# BW1098OBC_RIGHT_OV9282.net
KiCad netlist of a schematic drawn in Altium Designer
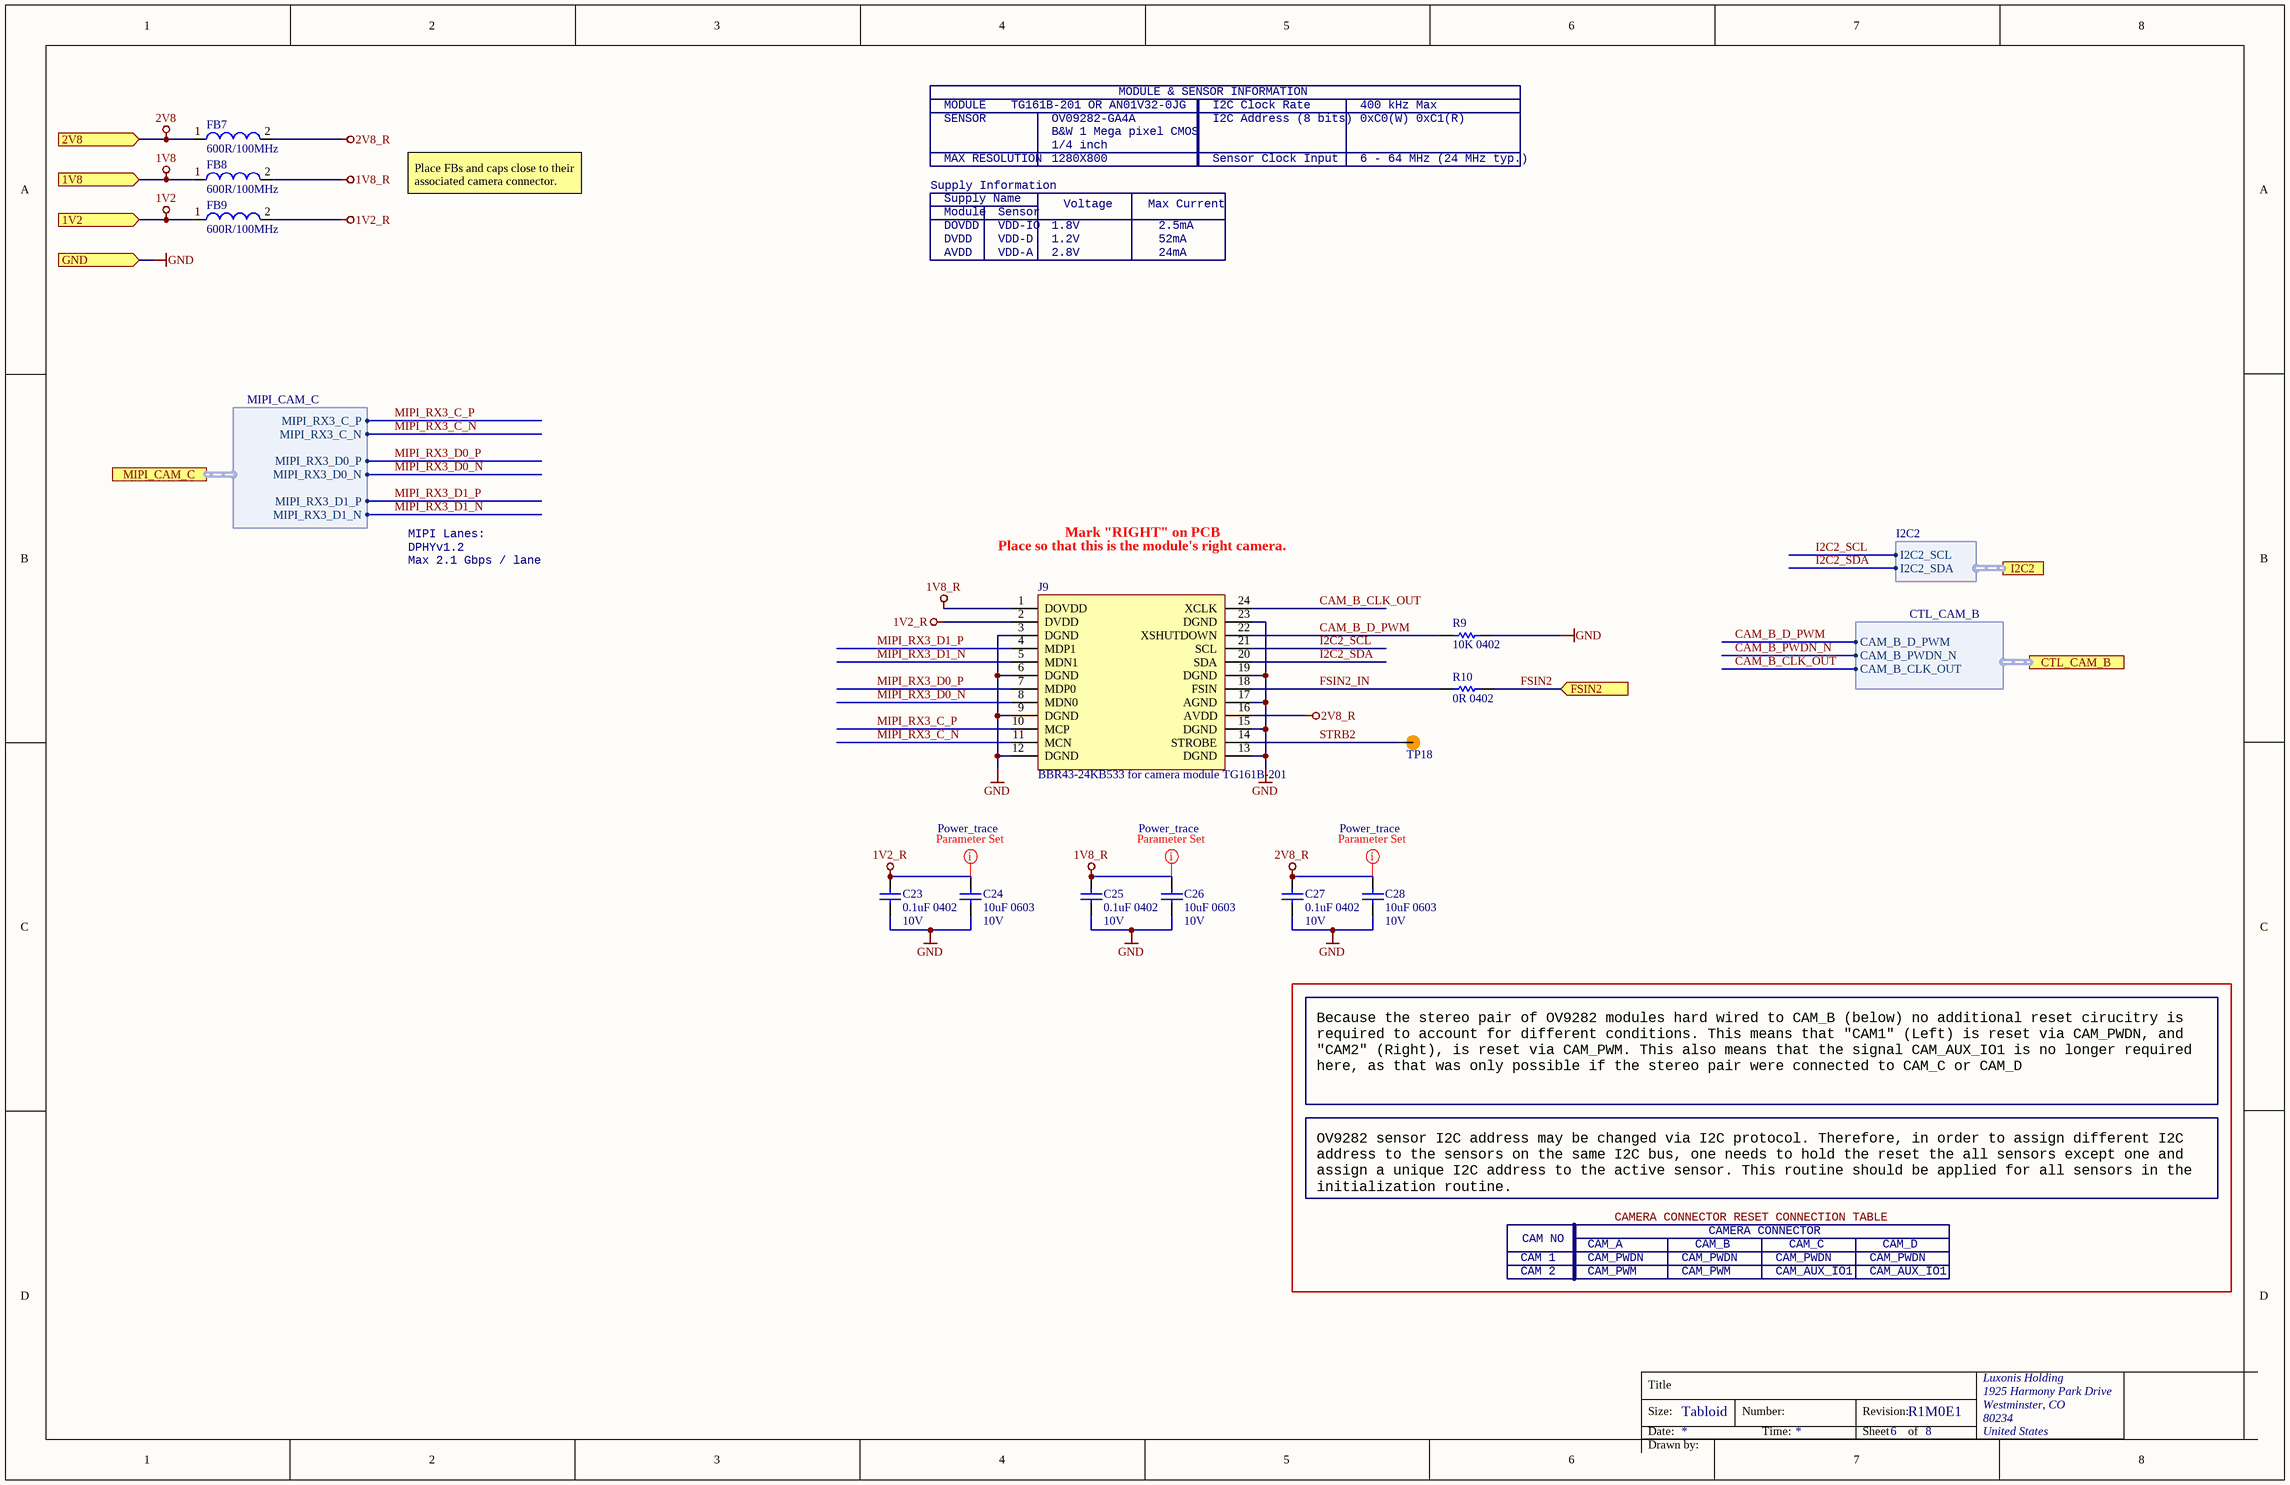
[diagram p0: BW1098OBC_RIGHT_OV9282.SchDoc]

(export (version "E")
  (design (tool "Eeschema 10.0.6"))
  (components
    (comp (ref "C23")
      (value "0.1uF 0402")
      (footprint "CAP_Altium_Vault_Generic:CAPC0402(1005)70_L")
      (description "CAP CER 0.1UF 10V X7R 0402 5%")
      (fields (field (name "TOLERANCE") "5%") (field (name "VOLTAGE RATING") "10V"))
      (libsource (lib "LuxonisMaster") (part "GRM155R71A104JA01D"))
    )
    (comp (ref "C24")
      (value "10uF 0603")
      (footprint "CAP_Altium_Vault_Generic:CAPC0603(1608)100_L")
      (description "CAP CER 10UF 10V X5R 0603 20%")
      (fields (field (name "TOLERANCE") "20%") (field (name "VOLTAGE RATING") "10V"))
      (libsource (lib "LuxonisMaster") (part "GRM188R61A106ME69D"))
    )
    (comp (ref "C25")
      (value "0.1uF 0402")
      (footprint "CAP_Altium_Vault_Generic:CAPC0402(1005)70_L")
      (description "CAP CER 0.1UF 10V X7R 0402 5%")
      (fields (field (name "TOLERANCE") "5%") (field (name "VOLTAGE RATING") "10V"))
      (libsource (lib "LuxonisMaster") (part "GRM155R71A104JA01D"))
    )
    (comp (ref "C26")
      (value "10uF 0603")
      (footprint "CAP_Altium_Vault_Generic:CAPC0603(1608)100_L")
      (description "CAP CER 10UF 10V X5R 0603 20%")
      (fields (field (name "TOLERANCE") "20%") (field (name "VOLTAGE RATING") "10V"))
      (libsource (lib "LuxonisMaster") (part "GRM188R61A106ME69D"))
    )
    (comp (ref "C27")
      (value "0.1uF 0402")
      (footprint "CAP_Altium_Vault_Generic:CAPC0402(1005)70_L")
      (description "CAP CER 0.1UF 10V X7R 0402 5%")
      (fields (field (name "TOLERANCE") "5%") (field (name "VOLTAGE RATING") "10V"))
      (libsource (lib "LuxonisMaster") (part "GRM155R71A104JA01D"))
    )
    (comp (ref "C28")
      (value "10uF 0603")
      (footprint "CAP_Altium_Vault_Generic:CAPC0603(1608)100_L")
      (description "CAP CER 10UF 10V X5R 0603 20%")
      (fields (field (name "TOLERANCE") "20%") (field (name "VOLTAGE RATING") "10V"))
      (libsource (lib "LuxonisMaster") (part "GRM188R61A106ME69D"))
    )
    (comp (ref "FB7")
      (value "600R/100MHz")
      (footprint "LuxonisMaster:2508056017Y2")
      (description "FERRITE BEAD, 0.1OHM, 2A, 0805, 600R/100MHz")
      (fields (field (name "TOLERANCE") "25%"))
      (libsource (lib "LuxonisMaster") (part "2508056017Y2"))
    )
    (comp (ref "FB8")
      (value "600R/100MHz")
      (footprint "LuxonisMaster:2508056017Y2")
      (description "FERRITE BEAD, 0.1OHM, 2A, 0805, 600R/100MHz")
      (fields (field (name "TOLERANCE") "25%"))
      (libsource (lib "LuxonisMaster") (part "2508056017Y2"))
    )
    (comp (ref "FB9")
      (value "600R/100MHz")
      (footprint "LuxonisMaster:2508056017Y2")
      (description "FERRITE BEAD, 0.1OHM, 2A, 0805, 600R/100MHz")
      (fields (field (name "TOLERANCE") "25%"))
      (libsource (lib "LuxonisMaster") (part "2508056017Y2"))
    )
    (comp (ref "J9")
      (value "BBR43-24KB533 for camera module TG161B-201")
      (footprint "BW1098OBC:TG161B-201 / AN01V32 - Board Wrap (7mm setback) MinPads")
      (description "CONN 24 way, 2 row board to board connector SMD")
      (fields (field (name "MANUFACTURER") "ACON"))
      (libsource (lib "LuxonisMaster") (part "TG161B-201_Connector"))
    )
    (comp (ref "R9")
      (value "10K 0402")
      (footprint "RES_Altium_Vault_Generic:RESC0402(1005)_L")
      (fields (field (name "TOLERANCE") "1%"))
      (libsource (lib "LuxonisMaster") (part "RC0402FR-1310KL"))
    )
    (comp (ref "R10")
      (value "0R 0402")
      (footprint "RES_Altium_Vault_Generic:RESC0402(1005)_L")
      (description "RES SMD 0 OHM JUMPER 1/16W 0402")
      (fields (field (name "TOLERANCE") "5%"))
      (libsource (lib "LuxonisMaster") (part "CRCW04020000Z0ED"))
    )
    (comp (ref "TP18")
      (value "TP100_200_NS")
      (footprint "LuxonisMaster:TP100_200_NS")
      (libsource (lib "LuxonisMaster") (part "TEST_POINT"))
    )
  )
  (nets
    (net (code "4") (name "/CAM_B_CLK_OUT") (class "Default")
      (node (ref "J9") (pin "24") (pinfunction "XCLK_24") (pintype "passive"))
    )
    (net (code "5") (name "/CAM_B_D_PWM") (class "Default")
      (node (ref "J9") (pin "22") (pinfunction "XSHUTDOWN_22") (pintype "passive"))
      (node (ref "R9") (pin "1") (pinfunction "1_1") (pintype "passive"))
    )
    (net (code "7") (name "/FSIN2") (class "Default")
      (node (ref "R10") (pin "2") (pinfunction "2_2") (pintype "passive"))
    )
    (net (code "8") (name "/FSIN2_IN") (class "Default")
      (node (ref "J9") (pin "18") (pinfunction "FSIN_18") (pintype "passive"))
      (node (ref "R10") (pin "1") (pinfunction "1_1") (pintype "passive"))
    )
    (net (code "9") (name "/I2C2_SCL") (class "Default")
      (node (ref "J9") (pin "21") (pinfunction "SCL_21") (pintype "passive"))
    )
    (net (code "10") (name "/I2C2_SDA") (class "Default")
      (node (ref "J9") (pin "20") (pinfunction "SDA_20") (pintype "passive"))
    )
    (net (code "11") (name "/MIPI_RX3_C_N") (class "Default")
      (node (ref "J9") (pin "11") (pinfunction "MCN_11") (pintype "passive"))
    )
    (net (code "12") (name "/MIPI_RX3_C_P") (class "Default")
      (node (ref "J9") (pin "10") (pinfunction "MCP_10") (pintype "passive"))
    )
    (net (code "13") (name "/MIPI_RX3_D0_N") (class "Default")
      (node (ref "J9") (pin "8") (pinfunction "MDN0_8") (pintype "passive"))
    )
    (net (code "14") (name "/MIPI_RX3_D0_P") (class "Default")
      (node (ref "J9") (pin "7") (pinfunction "MDP0_7") (pintype "passive"))
    )
    (net (code "15") (name "/MIPI_RX3_D1_N") (class "Default")
      (node (ref "J9") (pin "5") (pinfunction "MDN1_5") (pintype "passive"))
    )
    (net (code "16") (name "/MIPI_RX3_D1_P") (class "Default")
      (node (ref "J9") (pin "4") (pinfunction "MDP1_4") (pintype "passive"))
    )
    (net (code "17") (name "/STRB2") (class "Default")
      (node (ref "J9") (pin "14") (pinfunction "STROBE_14") (pintype "passive"))
      (node (ref "TP18") (pin "1") (pintype "passive"))
    )
    (net (code "21") (name "1V2") (class "Default")
      (node (ref "FB9") (pin "1") (pinfunction "1_1") (pintype "passive"))
    )
    (net (code "22") (name "1V2_R") (class "Default")
      (node (ref "C23") (pin "2") (pinfunction "2_2") (pintype "passive"))
      (node (ref "C24") (pin "2") (pinfunction "2_2") (pintype "passive"))
      (node (ref "FB9") (pin "2") (pinfunction "2_2") (pintype "passive"))
      (node (ref "J9") (pin "2") (pinfunction "DVDD_2") (pintype "passive"))
    )
    (net (code "23") (name "1V8") (class "Default")
      (node (ref "FB8") (pin "1") (pinfunction "1_1") (pintype "passive"))
    )
    (net (code "24") (name "1V8_R") (class "Default")
      (node (ref "C25") (pin "2") (pinfunction "2_2") (pintype "passive"))
      (node (ref "C26") (pin "2") (pinfunction "2_2") (pintype "passive"))
      (node (ref "FB8") (pin "2") (pinfunction "2_2") (pintype "passive"))
      (node (ref "J9") (pin "1") (pinfunction "DOVDD_1") (pintype "passive"))
    )
    (net (code "25") (name "2V8") (class "Default")
      (node (ref "FB7") (pin "1") (pinfunction "1_1") (pintype "passive"))
    )
    (net (code "26") (name "2V8_R") (class "Default")
      (node (ref "C27") (pin "2") (pinfunction "2_2") (pintype "passive"))
      (node (ref "C28") (pin "2") (pinfunction "2_2") (pintype "passive"))
      (node (ref "FB7") (pin "2") (pinfunction "2_2") (pintype "passive"))
      (node (ref "J9") (pin "16") (pinfunction "AVDD_16") (pintype "passive"))
    )
    (net (code "27") (name "GND") (class "Default")
      (node (ref "C23") (pin "1") (pinfunction "1_1") (pintype "passive"))
      (node (ref "C24") (pin "1") (pinfunction "1_1") (pintype "passive"))
      (node (ref "C25") (pin "1") (pinfunction "1_1") (pintype "passive"))
      (node (ref "C26") (pin "1") (pinfunction "1_1") (pintype "passive"))
      (node (ref "C27") (pin "1") (pinfunction "1_1") (pintype "passive"))
      (node (ref "C28") (pin "1") (pinfunction "1_1") (pintype "passive"))
      (node (ref "J9") (pin "12") (pinfunction "DGND_12") (pintype "passive"))
      (node (ref "J9") (pin "13") (pinfunction "DGND_13") (pintype "passive"))
      (node (ref "J9") (pin "15") (pinfunction "DGND_15") (pintype "passive"))
      (node (ref "J9") (pin "17") (pinfunction "AGND_17") (pintype "passive"))
      (node (ref "J9") (pin "19") (pinfunction "DGND_19") (pintype "passive"))
      (node (ref "J9") (pin "23") (pinfunction "DGND_23") (pintype "passive"))
      (node (ref "J9") (pin "3") (pinfunction "DGND_3") (pintype "passive"))
      (node (ref "J9") (pin "6") (pinfunction "DGND_6") (pintype "passive"))
      (node (ref "J9") (pin "9") (pinfunction "DGND_9") (pintype "passive"))
      (node (ref "R9") (pin "2") (pinfunction "2_2") (pintype "passive"))
    )
  )
)
